# Humidifier.net
KiCad netlist of a schematic drawn in Altium Designer
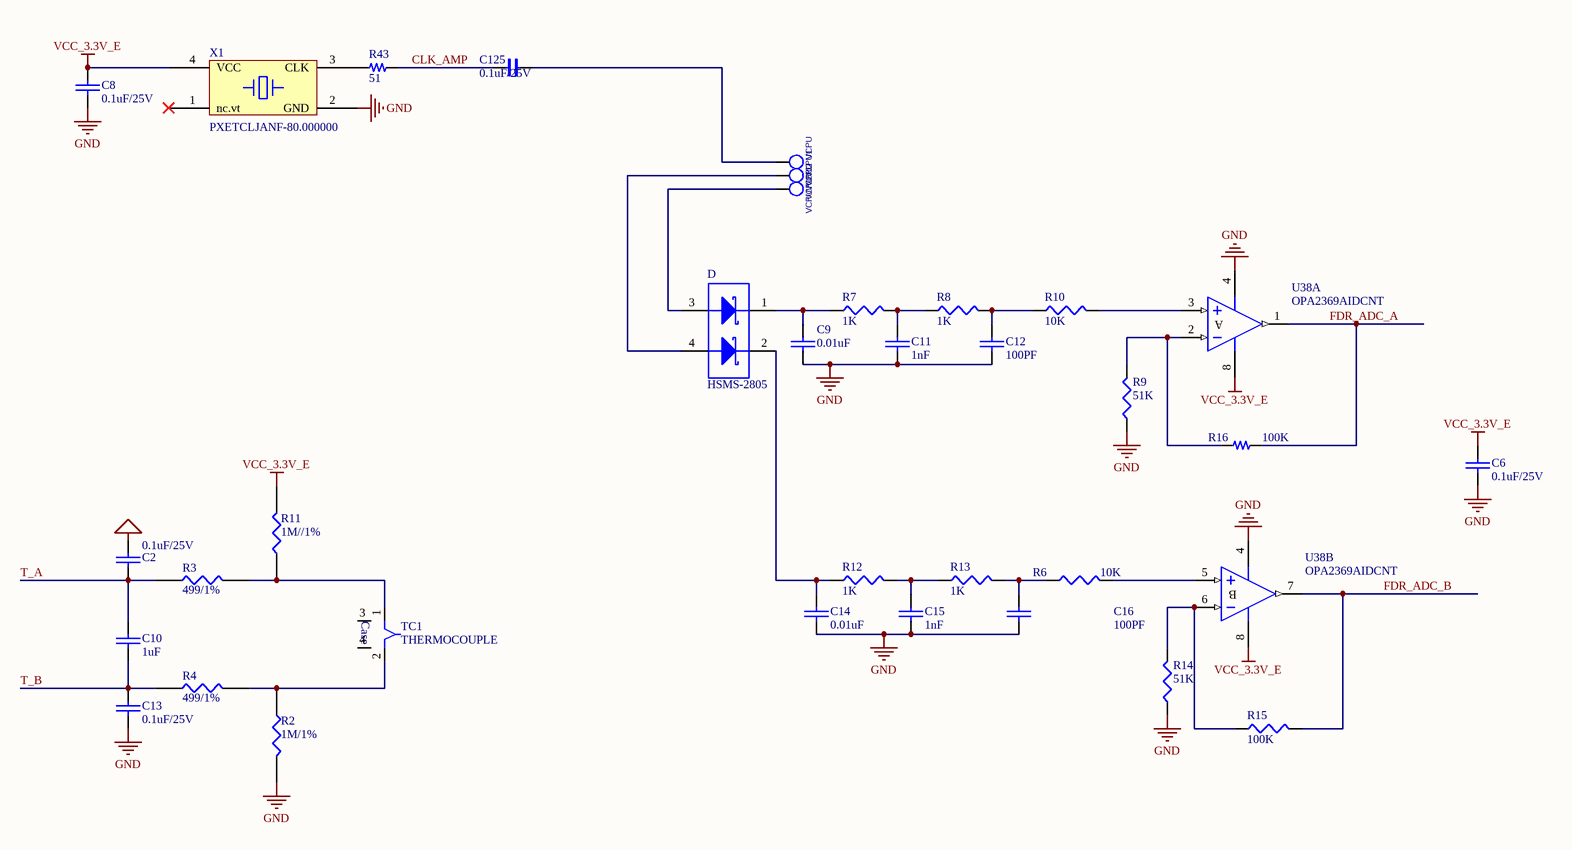
[diagram p0: Humidifier.SchDoc]

(export (version "E")
  (design (tool "Eeschema 10.0.6"))
  (components
    (comp (ref "C2")
      (value "0.1uF/25V")
      (footprint "0603c")
      (description "Capacitor")
      (libsource (lib "*") (part "CAP"))
    )
    (comp (ref "C6")
      (value "0.1uF/25V")
      (footprint "0603C")
      (description "Capacitor")
      (libsource (lib "SM") (part "CAP"))
    )
    (comp (ref "C8")
      (value "0.1uF/25V")
      (footprint "0603C")
      (description "Capacitor")
      (libsource (lib "SM") (part "CAP"))
    )
    (comp (ref "C9")
      (value "0.01uF")
      (footprint "0603C")
      (description "Capacitor")
      (libsource (lib "SM") (part "CAP"))
    )
    (comp (ref "C10")
      (value "1uF")
      (footprint "0603c")
      (description "Capacitor")
      (libsource (lib "*") (part "CAP"))
    )
    (comp (ref "C11")
      (value "1nF")
      (footprint "0603C")
      (description "Capacitor")
      (libsource (lib "SM") (part "CAP"))
    )
    (comp (ref "C12")
      (value "100PF")
      (footprint "0603C")
      (description "Capacitor")
      (libsource (lib "SM") (part "CAP"))
    )
    (comp (ref "C13")
      (value "0.1uF/25V")
      (footprint "0603c")
      (description "Capacitor")
      (libsource (lib "*") (part "CAP"))
    )
    (comp (ref "C14")
      (value "0.01uF")
      (footprint "0603C")
      (description "Capacitor")
      (libsource (lib "SM") (part "CAP"))
    )
    (comp (ref "C15")
      (value "1nF")
      (footprint "0603C")
      (description "Capacitor")
      (libsource (lib "SM") (part "CAP"))
    )
    (comp (ref "C16")
      (value "100PF")
      (footprint "0603C")
      (description "Capacitor")
      (libsource (lib "SM") (part "CAP"))
    )
    (comp (ref "C125")
      (value "0.1uF/25V")
      (footprint "0603C")
      (description "C")
      (libsource (lib "YxmSCH") (part "C"))
    )
    (comp (ref "D")
      (value "HSMS-2805")
      (footprint "HSMS-2805")
      (libsource (lib "Schlib_20110825") (part "HSMS-2805"))
    )
    (comp (ref "R2") (value "1M/1%") (footprint "0603r") (libsource (lib "*") (part "RES1")))
    (comp (ref "R3") (value "499/1%") (footprint "0603r") (libsource (lib "*") (part "RES1")))
    (comp (ref "R4") (value "499/1%") (footprint "0603r") (libsource (lib "*") (part "RES1")))
    (comp (ref "R6")
      (value "10K")
      (footprint "0603R")
      (description "Resistor")
      (fields (field (name "PUBLISHER") "Altium Limited"))
      (libsource (lib "SM") (part "Res3"))
    )
    (comp (ref "R7")
      (value "1K")
      (footprint "0603R")
      (description "Resistor")
      (fields (field (name "PUBLISHER") "Altium Limited"))
      (libsource (lib "SM") (part "Res3"))
    )
    (comp (ref "R8")
      (value "1K")
      (footprint "0603R")
      (description "Resistor")
      (fields (field (name "PUBLISHER") "Altium Limited"))
      (libsource (lib "SM") (part "Res3"))
    )
    (comp (ref "R9")
      (value "51K")
      (footprint "0603R")
      (description "Resistor")
      (fields (field (name "PUBLISHER") "Altium Limited"))
      (libsource (lib "SM") (part "Res3"))
    )
    (comp (ref "R10")
      (value "10K")
      (footprint "0603R")
      (description "Resistor")
      (fields (field (name "PUBLISHER") "Altium Limited"))
      (libsource (lib "SM") (part "Res3"))
    )
    (comp (ref "R11") (value "1M//1%") (footprint "0603r") (libsource (lib "*") (part "RES1")))
    (comp (ref "R12")
      (value "1K")
      (footprint "0603R")
      (description "Resistor")
      (fields (field (name "PUBLISHER") "Altium Limited"))
      (libsource (lib "SM") (part "Res3"))
    )
    (comp (ref "R13")
      (value "1K")
      (footprint "0603R")
      (description "Resistor")
      (fields (field (name "PUBLISHER") "Altium Limited"))
      (libsource (lib "SM") (part "Res3"))
    )
    (comp (ref "R14")
      (value "51K")
      (footprint "0603R")
      (description "Resistor")
      (fields (field (name "PUBLISHER") "Altium Limited"))
      (libsource (lib "SM") (part "Res3"))
    )
    (comp (ref "R15")
      (value "100K")
      (footprint "0603R")
      (description "Resistor")
      (fields (field (name "PUBLISHER") "Altium Limited"))
      (libsource (lib "SM") (part "Res3"))
    )
    (comp (ref "R16")
      (value "100K")
      (footprint "0603R")
      (description "R")
      (libsource (lib "JRJ_1") (part "R"))
    )
    (comp (ref "R43") (value "51") (footprint "0603r") (description "R") (libsource (lib "JRJ") (part "R")))
    (comp (ref "TC1") (value "THERMOCOUPLE") (footprint "0603R") (libsource (lib "*") (part "THERMOCOUPLE")))
    (comp (ref "U38")
      (value "OPA2369AIDCNT")
      (footprint "OPA2369AIDCNT")
      (description "Dual Operational Amplifier")
      (fields (field (name "PUBLISHER") "Altium Limited"))
      (libsource (lib "stm32") (part "LM2904D"))
    )
    (comp (ref "VCPU") (value "VCPU") (footprint "probe") (libsource (lib "*") (part "T_POINT_R")))
    (comp (ref "VCPU1") (value "VCPU") (footprint "probe") (libsource (lib "*") (part "T_POINT_R")))
    (comp (ref "VCPU2") (value "VCPU") (footprint "probe") (libsource (lib "*") (part "T_POINT_R")))
    (comp (ref "X1")
      (value "PXETCLJANF-80.000000")
      (footprint "XTAL4TN_7050")
      (libsource (lib "Y0801_V13") (part "XTAL4S"))
    )
  )
  (nets
    (net (code "1") (name "/CLK_AMP") (class "Default")
      (node (ref "C125") (pin "1") (pintype "passive"))
      (node (ref "R43") (pin "2") (pintype "passive"))
    )
    (net (code "2") (name "/FDR_ADC_A") (class "Default")
      (node (ref "R16") (pin "2") (pintype "passive"))
      (node (ref "U38") (pin "1") (pinfunction "OUT_1") (pintype "output"))
    )
    (net (code "3") (name "/FDR_ADC_B") (class "Default")
      (node (ref "R15") (pin "2") (pinfunction "2_2") (pintype "passive"))
      (node (ref "U38") (pin "7") (pinfunction "OUT_7") (pintype "output"))
    )
    (net (code "4") (name "/T_A") (class "Default")
      (node (ref "C10") (pin "1") (pinfunction "1_1") (pintype "passive"))
      (node (ref "C2") (pin "1") (pinfunction "1_1") (pintype "passive"))
      (node (ref "R3") (pin "1") (pinfunction "1_1") (pintype "passive"))
    )
    (net (code "5") (name "/T_B") (class "Default")
      (node (ref "C10") (pin "2") (pinfunction "2_2") (pintype "passive"))
      (node (ref "C13") (pin "1") (pinfunction "1_1") (pintype "passive"))
      (node (ref "R4") (pin "1") (pinfunction "1_1") (pintype "passive"))
    )
    (net (code "6") (name "GND") (class "Default")
      (node (ref "C11") (pin "2") (pinfunction "2_2") (pintype "passive"))
      (node (ref "C12") (pin "2") (pinfunction "2_2") (pintype "passive"))
      (node (ref "C13") (pin "2") (pinfunction "2_2") (pintype "passive"))
      (node (ref "C14") (pin "2") (pinfunction "2_2") (pintype "passive"))
      (node (ref "C15") (pin "2") (pinfunction "2_2") (pintype "passive"))
      (node (ref "C16") (pin "2") (pinfunction "2_2") (pintype "passive"))
      (node (ref "C2") (pin "2") (pinfunction "2_2") (pintype "passive"))
      (node (ref "C6") (pin "1") (pinfunction "1_1") (pintype "passive"))
      (node (ref "C8") (pin "2") (pinfunction "2_2") (pintype "passive"))
      (node (ref "C9") (pin "2") (pinfunction "2_2") (pintype "passive"))
      (node (ref "R14") (pin "1") (pinfunction "1_1") (pintype "passive"))
      (node (ref "R2") (pin "2") (pinfunction "2_2") (pintype "passive"))
      (node (ref "R9") (pin "1") (pinfunction "1_1") (pintype "passive"))
      (node (ref "U38") (pin "4") (pinfunction "V-_4") (pintype "power_in"))
      (node (ref "X1") (pin "2") (pinfunction "GND_2") (pintype "power_in"))
    )
    (net (code "7") (name "Net-(C9-Pad1)") (class "Default")
      (node (ref "C9") (pin "1") (pinfunction "1_1") (pintype "passive"))
      (node (ref "D") (pin "1") (pinfunction "K_1") (pintype "passive"))
      (node (ref "R7") (pin "1") (pinfunction "1_1") (pintype "passive"))
    )
    (net (code "8") (name "Net-(C11-Pad1)") (class "Default")
      (node (ref "C11") (pin "1") (pinfunction "1_1") (pintype "passive"))
      (node (ref "R7") (pin "2") (pinfunction "2_2") (pintype "passive"))
      (node (ref "R8") (pin "1") (pinfunction "1_1") (pintype "passive"))
    )
    (net (code "9") (name "Net-(C12-Pad1)") (class "Default")
      (node (ref "C12") (pin "1") (pinfunction "1_1") (pintype "passive"))
      (node (ref "R10") (pin "1") (pinfunction "1_1") (pintype "passive"))
      (node (ref "R8") (pin "2") (pinfunction "2_2") (pintype "passive"))
    )
    (net (code "10") (name "Net-(C14-Pad1)") (class "Default")
      (node (ref "C14") (pin "1") (pinfunction "1_1") (pintype "passive"))
      (node (ref "D") (pin "2") (pinfunction "K_2") (pintype "passive"))
      (node (ref "R12") (pin "1") (pinfunction "1_1") (pintype "passive"))
    )
    (net (code "11") (name "Net-(C15-Pad1)") (class "Default")
      (node (ref "C15") (pin "1") (pinfunction "1_1") (pintype "passive"))
      (node (ref "R12") (pin "2") (pinfunction "2_2") (pintype "passive"))
      (node (ref "R13") (pin "1") (pinfunction "1_1") (pintype "passive"))
    )
    (net (code "12") (name "Net-(C16-Pad1)") (class "Default")
      (node (ref "C16") (pin "1") (pinfunction "1_1") (pintype "passive"))
      (node (ref "R13") (pin "2") (pinfunction "2_2") (pintype "passive"))
      (node (ref "R6") (pin "1") (pinfunction "1_1") (pintype "passive"))
    )
    (net (code "13") (name "Net-(R2-Pad1)") (class "Default")
      (node (ref "R2") (pin "1") (pinfunction "1_1") (pintype "passive"))
      (node (ref "R4") (pin "2") (pinfunction "2_2") (pintype "passive"))
      (node (ref "TC1") (pin "2") (pinfunction "2_2") (pintype "passive"))
    )
    (net (code "14") (name "Net-(R11-Pad1)") (class "Default")
      (node (ref "R11") (pin "1") (pinfunction "1_1") (pintype "passive"))
      (node (ref "R3") (pin "2") (pinfunction "2_2") (pintype "passive"))
      (node (ref "TC1") (pin "1") (pinfunction "1_1") (pintype "passive"))
    )
    (net (code "15") (name "Net-(U38A-IN+)") (class "Default")
      (node (ref "R10") (pin "2") (pinfunction "2_2") (pintype "passive"))
      (node (ref "U38") (pin "3") (pinfunction "IN+_3") (pintype "input"))
    )
    (net (code "16") (name "Net-(U38A-IN-)") (class "Default")
      (node (ref "R16") (pin "1") (pintype "passive"))
      (node (ref "R9") (pin "2") (pinfunction "2_2") (pintype "passive"))
      (node (ref "U38") (pin "2") (pinfunction "IN-_2") (pintype "input"))
    )
    (net (code "17") (name "Net-(U38B-IN+)") (class "Default")
      (node (ref "R6") (pin "2") (pinfunction "2_2") (pintype "passive"))
      (node (ref "U38") (pin "5") (pinfunction "IN+_5") (pintype "input"))
    )
    (net (code "18") (name "Net-(U38B-IN-)") (class "Default")
      (node (ref "R14") (pin "2") (pinfunction "2_2") (pintype "passive"))
      (node (ref "R15") (pin "1") (pinfunction "1_1") (pintype "passive"))
      (node (ref "U38") (pin "6") (pinfunction "IN-_6") (pintype "input"))
    )
    (net (code "19") (name "Net-(VCPU-TP)") (class "Default")
      (node (ref "C125") (pin "2") (pintype "passive"))
      (node (ref "VCPU") (pin "1") (pinfunction "TP_1") (pintype "passive"))
    )
    (net (code "20") (name "Net-(VCPU1-TP)") (class "Default")
      (node (ref "D") (pin "4") (pinfunction "A_4") (pintype "passive"))
      (node (ref "VCPU1") (pin "1") (pinfunction "TP_1") (pintype "passive"))
    )
    (net (code "21") (name "Net-(VCPU2-TP)") (class "Default")
      (node (ref "D") (pin "3") (pinfunction "A_3") (pintype "passive"))
      (node (ref "VCPU2") (pin "1") (pinfunction "TP_1") (pintype "passive"))
    )
    (net (code "22") (name "Net-(X1-CLK)") (class "Default")
      (node (ref "R43") (pin "1") (pintype "passive"))
      (node (ref "X1") (pin "3") (pinfunction "CLK_3") (pintype "passive"))
    )
    (net (code "23") (name "VCC_3.3V_E") (class "Default")
      (node (ref "C6") (pin "2") (pinfunction "2_2") (pintype "passive"))
      (node (ref "C8") (pin "1") (pinfunction "1_1") (pintype "passive"))
      (node (ref "R11") (pin "2") (pinfunction "2_2") (pintype "passive"))
      (node (ref "U38") (pin "8") (pinfunction "V+_8") (pintype "power_in"))
      (node (ref "X1") (pin "4") (pinfunction "VCC_4") (pintype "power_in"))
    )
    (net (code "24") (name "unconnected-(TC1-Pad3)") (class "Default")
      (node (ref "TC1") (pin "3") (pinfunction "3_3") (pintype "passive"))
    )
    (net (code "25") (name "unconnected-(TC1-Pad4)") (class "Default")
      (node (ref "TC1") (pin "4") (pinfunction "4_4") (pintype "passive"))
    )
    (net (code "26") (name "unconnected-(X1-nc.vt-Pad1)") (class "Default")
      (node (ref "X1") (pin "1") (pinfunction "nc.vt_1") (pintype "passive+no_connect"))
    )
  )
)
